# NL.net
KiCad netlist of a schematic drawn in Altium Designer
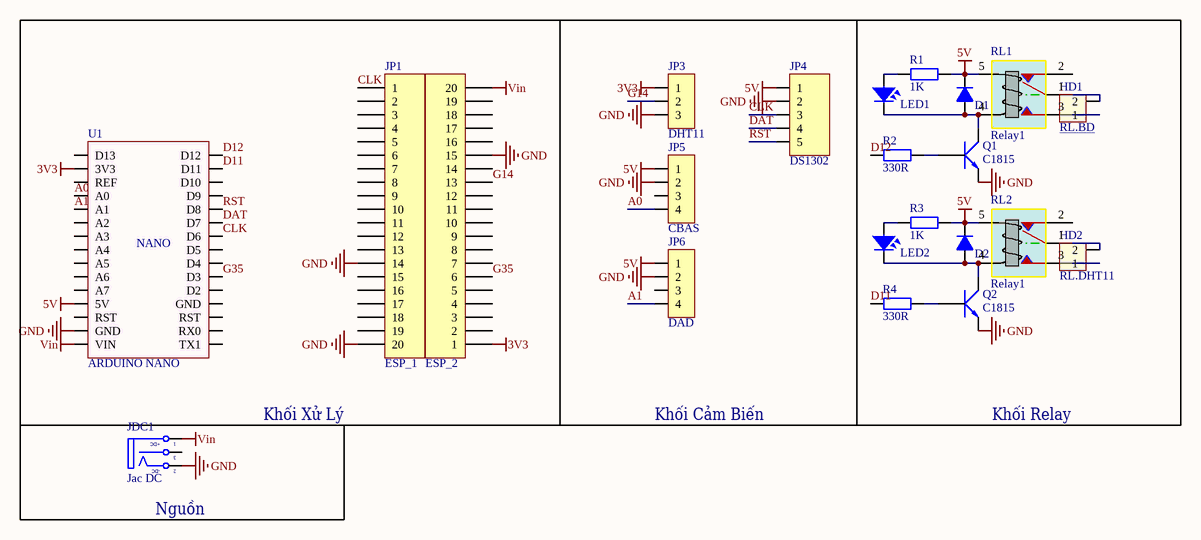
[diagram p0: NL.SchDoc]

(export (version "E")
  (design (tool "Eeschema 10.0.6"))
  (components
    (comp (ref "D1")
      (value "4007")
      (footprint "DIODE 1A")
      (description "Cắm")
      (libsource (lib "Altium_Lib_by_KhueNguyenCreator") (part "Diode 1N4007"))
    )
    (comp (ref "D2")
      (value "4007")
      (footprint "DIODE 1A")
      (description "Cắm")
      (libsource (lib "Altium_Lib_by_KhueNguyenCreator") (part "Diode 1N4007"))
    )
    (comp (ref "HD1")
      (value "RL.BD")
      (footprint "HED2")
      (description "Header 2 (Green)")
      (libsource (lib "syhaunguyen") (part "Hed2"))
    )
    (comp (ref "HD2")
      (value "RL.DHT11")
      (footprint "HED2")
      (description "Header 2 (Green)")
      (libsource (lib "syhaunguyen") (part "Hed2"))
    )
    (comp (ref "JDC1")
      (value "Jac DC")
      (footprint "DC-IN")
      (description "Jac DC input")
      (libsource (lib "syhaunguyen") (part "DCIN"))
    )
    (comp (ref "JP1")
      (value "ESP_1")
      (footprint "JP 1x20 CT")
      (description "Cắm")
      (libsource (lib "") (part "JP 1x20 2.54 Cai Thang_1"))
    )
    (comp (ref "JP2")
      (value "ESP_2")
      (footprint "JP 1x20 CT")
      (description "Cắm")
      (libsource (lib "Altium_Lib_by_KhueNguyenCreator") (part "JP 1x20 2.54 Cai Thang"))
    )
    (comp (ref "JP3")
      (value "DHT11")
      (footprint "JP 1x3 CT")
      (description "Cắm")
      (libsource (lib "Altium_Lib_by_KhueNguyenCreator") (part "JP 1x3 2.54 Cai Thang"))
    )
    (comp (ref "JP4")
      (value "DS1302")
      (footprint "JP 1x5 CT")
      (description "Cắm")
      (libsource (lib "Altium_Lib_by_KhueNguyenCreator") (part "JP 1x5 2.54 Cai Thang"))
    )
    (comp (ref "JP5")
      (value "CBAS")
      (footprint "JP 1x4 CT")
      (description "Cắm")
      (libsource (lib "Altium_Lib_by_KhueNguyenCreator") (part "JP 1x4 2.54 Cai Thang"))
    )
    (comp (ref "JP6")
      (value "DAD")
      (footprint "JP 1x4 CT")
      (description "Cắm")
      (libsource (lib "Altium_Lib_by_KhueNguyenCreator") (part "JP 1x4 2.54 Cai Thang"))
    )
    (comp (ref "LED1")
      (value "LED")
      (footprint "LED-3")
      (description "LED Single colour Green and Red")
      (libsource (lib "syhaunguyen") (part "LED"))
    )
    (comp (ref "LED2")
      (value "LED")
      (footprint "LED-3")
      (description "LED Single colour Green and Red")
      (libsource (lib "syhaunguyen") (part "LED"))
    )
    (comp (ref "Q1")
      (value "C1815")
      (footprint "TO92")
      (description "NPN transistor")
      (libsource (lib "Altium_Lib_by_KhueNguyenCreator") (part "C1815"))
    )
    (comp (ref "Q2")
      (value "C1815")
      (footprint "TO92")
      (description "NPN transistor")
      (libsource (lib "Altium_Lib_by_KhueNguyenCreator") (part "C1815"))
    )
    (comp (ref "R1")
      (value "1K")
      (footprint "R1/4W")
      (description "Resistor 1/4W")
      (libsource (lib "syhaunguyen") (part "R1/4W"))
    )
    (comp (ref "R2")
      (value "330R")
      (footprint "R1/4W")
      (description "Resistor 1/4W")
      (libsource (lib "syhaunguyen") (part "R1/4W"))
    )
    (comp (ref "R3")
      (value "1K")
      (footprint "R1/4W")
      (description "Resistor 1/4W")
      (libsource (lib "syhaunguyen") (part "R1/4W"))
    )
    (comp (ref "R4")
      (value "330R")
      (footprint "R1/4W")
      (description "Resistor 1/4W")
      (libsource (lib "syhaunguyen") (part "R1/4W"))
    )
    (comp (ref "RL1")
      (value "Relay1")
      (footprint "RELAY1")
      (description "Relay SPDT,10A - 12VDC 5 Pin")
      (libsource (lib "tham_khanh") (part "Relay1"))
    )
    (comp (ref "RL2")
      (value "Relay1")
      (footprint "RELAY1")
      (description "Relay SPDT,10A - 12VDC 5 Pin")
      (libsource (lib "tham_khanh") (part "Relay1"))
    )
    (comp (ref "U1")
      (value "ARDUINO NANO")
      (footprint "Arduino Nano")
      (description "ATMEGA328, ARDUINO NANO, EVAL BOARD")
      (libsource (lib "tham_khanh") (part "ARDUINO NANO"))
    )
  )
  (nets
    (net (code "1") (name "/A0") (class "Default")
      (node (ref "JP5") (pin "4") (pinfunction "4_4") (pintype "passive"))
      (node (ref "U1") (pin "A0") (pinfunction "A0_A0") (pintype "passive"))
    )
    (net (code "2") (name "/A1") (class "Default")
      (node (ref "JP6") (pin "4") (pinfunction "4_4") (pintype "passive"))
      (node (ref "U1") (pin "A1") (pinfunction "A1_A1") (pintype "passive"))
    )
    (net (code "3") (name "/CLK") (class "Default")
      (node (ref "JP1") (pin "1") (pinfunction "1_1") (pintype "passive"))
      (node (ref "JP4") (pin "3") (pinfunction "3_3") (pintype "passive"))
      (node (ref "U1") (pin "D6") (pinfunction "D6_D6") (pintype "passive"))
    )
    (net (code "4") (name "/D11") (class "Default")
      (node (ref "R4") (pin "1") (pinfunction "1_1") (pintype "passive"))
      (node (ref "U1") (pin "D11") (pinfunction "D11_D11") (pintype "passive"))
    )
    (net (code "5") (name "/D12") (class "Default")
      (node (ref "R2") (pin "1") (pinfunction "1_1") (pintype "passive"))
      (node (ref "U1") (pin "D12") (pinfunction "D12_D12") (pintype "passive"))
    )
    (net (code "6") (name "/DAT") (class "Default")
      (node (ref "JP4") (pin "4") (pinfunction "4_4") (pintype "passive"))
      (node (ref "U1") (pin "D7") (pinfunction "D7_D7") (pintype "passive"))
    )
    (net (code "7") (name "/G14") (class "Default")
      (node (ref "JP2") (pin "13") (pinfunction "13_13") (pintype "passive"))
      (node (ref "JP3") (pin "2") (pinfunction "2_2") (pintype "passive"))
    )
    (net (code "8") (name "/G35") (class "Default")
      (node (ref "JP2") (pin "6") (pinfunction "6_6") (pintype "passive"))
      (node (ref "U1") (pin "D3") (pinfunction "D3_D3") (pintype "passive"))
    )
    (net (code "9") (name "/RST") (class "Default")
      (node (ref "JP4") (pin "5") (pinfunction "5_5") (pintype "passive"))
      (node (ref "U1") (pin "D8") (pinfunction "D8_D8") (pintype "passive"))
    )
    (net (code "10") (name "3V3") (class "Default")
      (node (ref "JP2") (pin "1") (pinfunction "1_1") (pintype "passive"))
      (node (ref "JP3") (pin "1") (pinfunction "1_1") (pintype "passive"))
      (node (ref "U1") (pin "3V3") (pinfunction "3V3_3V3") (pintype "passive"))
    )
    (net (code "11") (name "5V") (class "Default")
      (node (ref "D1") (pin "2") (pinfunction "K_2") (pintype "passive"))
      (node (ref "D2") (pin "2") (pinfunction "K_2") (pintype "passive"))
      (node (ref "JP4") (pin "1") (pinfunction "1_1") (pintype "passive"))
      (node (ref "JP5") (pin "1") (pinfunction "1_1") (pintype "passive"))
      (node (ref "JP6") (pin "1") (pinfunction "1_1") (pintype "passive"))
      (node (ref "R1") (pin "2") (pinfunction "2_2") (pintype "passive"))
      (node (ref "R3") (pin "2") (pinfunction "2_2") (pintype "passive"))
      (node (ref "RL1") (pin "5") (pinfunction "5_5") (pintype "passive"))
      (node (ref "RL2") (pin "5") (pinfunction "5_5") (pintype "passive"))
      (node (ref "U1") (pin "5V") (pinfunction "5V_5V") (pintype "passive"))
    )
    (net (code "12") (name "GND") (class "Default")
      (node (ref "JDC1") (pin "2") (pinfunction "TN_2") (pintype "passive"))
      (node (ref "JP1") (pin "14") (pinfunction "14_14") (pintype "passive"))
      (node (ref "JP1") (pin "20") (pinfunction "20_20") (pintype "passive"))
      (node (ref "JP2") (pin "15") (pinfunction "15_15") (pintype "passive"))
      (node (ref "JP3") (pin "3") (pinfunction "3_3") (pintype "passive"))
      (node (ref "JP4") (pin "2") (pinfunction "2_2") (pintype "passive"))
      (node (ref "JP5") (pin "2") (pinfunction "2_2") (pintype "passive"))
      (node (ref "JP6") (pin "2") (pinfunction "2_2") (pintype "passive"))
      (node (ref "Q1") (pin "1") (pinfunction "E_1") (pintype "passive"))
      (node (ref "Q2") (pin "1") (pinfunction "E_1") (pintype "passive"))
      (node (ref "U1") (pin "GND") (pinfunction "GND_GND") (pintype "power_in"))
    )
    (net (code "13") (name "Net-(D1-A)") (class "Default")
      (node (ref "D1") (pin "1") (pinfunction "A_1") (pintype "passive"))
      (node (ref "LED1") (pin "2") (pinfunction "2_2") (pintype "passive"))
      (node (ref "Q1") (pin "2") (pinfunction "C_2") (pintype "passive"))
      (node (ref "RL1") (pin "4") (pinfunction "4_4") (pintype "passive"))
    )
    (net (code "14") (name "Net-(D2-A)") (class "Default")
      (node (ref "D2") (pin "1") (pinfunction "A_1") (pintype "passive"))
      (node (ref "LED2") (pin "2") (pinfunction "2_2") (pintype "passive"))
      (node (ref "Q2") (pin "2") (pinfunction "C_2") (pintype "passive"))
      (node (ref "RL2") (pin "4") (pinfunction "4_4") (pintype "passive"))
    )
    (net (code "15") (name "Net-(HD1-Pad1)") (class "Default")
      (node (ref "HD1") (pin "1") (pinfunction "1_1") (pintype "passive"))
      (node (ref "RL1") (pin "3") (pinfunction "3_3") (pintype "passive"))
    )
    (net (code "16") (name "Net-(HD1-Pad2)") (class "Default")
      (node (ref "HD1") (pin "2") (pinfunction "2_2") (pintype "passive"))
      (node (ref "RL1") (pin "1") (pinfunction "1_1") (pintype "passive"))
    )
    (net (code "17") (name "Net-(HD2-Pad1)") (class "Default")
      (node (ref "HD2") (pin "1") (pinfunction "1_1") (pintype "passive"))
      (node (ref "RL2") (pin "3") (pinfunction "3_3") (pintype "passive"))
    )
    (net (code "18") (name "Net-(HD2-Pad2)") (class "Default")
      (node (ref "HD2") (pin "2") (pinfunction "2_2") (pintype "passive"))
      (node (ref "RL2") (pin "1") (pinfunction "1_1") (pintype "passive"))
    )
    (net (code "19") (name "Net-(LED1-Pad1)") (class "Default")
      (node (ref "LED1") (pin "1") (pinfunction "1_1") (pintype "passive"))
      (node (ref "R1") (pin "1") (pinfunction "1_1") (pintype "passive"))
    )
    (net (code "20") (name "Net-(LED2-Pad1)") (class "Default")
      (node (ref "LED2") (pin "1") (pinfunction "1_1") (pintype "passive"))
      (node (ref "R3") (pin "1") (pinfunction "1_1") (pintype "passive"))
    )
    (net (code "21") (name "Net-(Q1-B)") (class "Default")
      (node (ref "Q1") (pin "3") (pinfunction "B_3") (pintype "passive"))
      (node (ref "R2") (pin "2") (pinfunction "2_2") (pintype "passive"))
    )
    (net (code "22") (name "Net-(Q2-B)") (class "Default")
      (node (ref "Q2") (pin "3") (pinfunction "B_3") (pintype "passive"))
      (node (ref "R4") (pin "2") (pinfunction "2_2") (pintype "passive"))
    )
    (net (code "23") (name "Vin") (class "Default")
      (node (ref "JDC1") (pin "1") (pinfunction "T_1") (pintype "passive"))
      (node (ref "JP2") (pin "20") (pinfunction "20_20") (pintype "passive"))
      (node (ref "U1") (pin "VIN") (pinfunction "VIN_VIN") (pintype "passive"))
    )
    (net (code "24") (name "unconnected-(JDC1-S-Pad3)") (class "Default")
      (node (ref "JDC1") (pin "3") (pinfunction "S_3") (pintype "power_in"))
    )
    (net (code "25") (name "unconnected-(JP1-Pad2)") (class "Default")
      (node (ref "JP1") (pin "2") (pinfunction "2_2") (pintype "passive"))
    )
    (net (code "26") (name "unconnected-(JP1-Pad3)") (class "Default")
      (node (ref "JP1") (pin "3") (pinfunction "3_3") (pintype "passive"))
    )
    (net (code "27") (name "unconnected-(JP1-Pad4)") (class "Default")
      (node (ref "JP1") (pin "4") (pinfunction "4_4") (pintype "passive"))
    )
    (net (code "28") (name "unconnected-(JP1-Pad5)") (class "Default")
      (node (ref "JP1") (pin "5") (pinfunction "5_5") (pintype "passive"))
    )
    (net (code "29") (name "unconnected-(JP1-Pad6)") (class "Default")
      (node (ref "JP1") (pin "6") (pinfunction "6_6") (pintype "passive"))
    )
    (net (code "30") (name "unconnected-(JP1-Pad7)") (class "Default")
      (node (ref "JP1") (pin "7") (pinfunction "7_7") (pintype "passive"))
    )
    (net (code "31") (name "unconnected-(JP1-Pad8)") (class "Default")
      (node (ref "JP1") (pin "8") (pinfunction "8_8") (pintype "passive"))
    )
    (net (code "32") (name "unconnected-(JP1-Pad9)") (class "Default")
      (node (ref "JP1") (pin "9") (pinfunction "9_9") (pintype "passive"))
    )
    (net (code "33") (name "unconnected-(JP1-Pad10)") (class "Default")
      (node (ref "JP1") (pin "10") (pinfunction "10_10") (pintype "passive"))
    )
    (net (code "34") (name "unconnected-(JP1-Pad11)") (class "Default")
      (node (ref "JP1") (pin "11") (pinfunction "11_11") (pintype "passive"))
    )
    (net (code "35") (name "unconnected-(JP1-Pad12)") (class "Default")
      (node (ref "JP1") (pin "12") (pinfunction "12_12") (pintype "passive"))
    )
    (net (code "36") (name "unconnected-(JP1-Pad13)") (class "Default")
      (node (ref "JP1") (pin "13") (pinfunction "13_13") (pintype "passive"))
    )
    (net (code "37") (name "unconnected-(JP1-Pad15)") (class "Default")
      (node (ref "JP1") (pin "15") (pinfunction "15_15") (pintype "passive"))
    )
    (net (code "38") (name "unconnected-(JP1-Pad16)") (class "Default")
      (node (ref "JP1") (pin "16") (pinfunction "16_16") (pintype "passive"))
    )
    (net (code "39") (name "unconnected-(JP1-Pad17)") (class "Default")
      (node (ref "JP1") (pin "17") (pinfunction "17_17") (pintype "passive"))
    )
    (net (code "40") (name "unconnected-(JP1-Pad18)") (class "Default")
      (node (ref "JP1") (pin "18") (pinfunction "18_18") (pintype "passive"))
    )
    (net (code "41") (name "unconnected-(JP1-Pad19)") (class "Default")
      (node (ref "JP1") (pin "19") (pinfunction "19_19") (pintype "passive"))
    )
    (net (code "42") (name "unconnected-(JP2-Pad2)") (class "Default")
      (node (ref "JP2") (pin "2") (pinfunction "2_2") (pintype "passive"))
    )
    (net (code "43") (name "unconnected-(JP2-Pad3)") (class "Default")
      (node (ref "JP2") (pin "3") (pinfunction "3_3") (pintype "passive"))
    )
    (net (code "44") (name "unconnected-(JP2-Pad4)") (class "Default")
      (node (ref "JP2") (pin "4") (pinfunction "4_4") (pintype "passive"))
    )
    (net (code "45") (name "unconnected-(JP2-Pad5)") (class "Default")
      (node (ref "JP2") (pin "5") (pinfunction "5_5") (pintype "passive"))
    )
    (net (code "46") (name "unconnected-(JP2-Pad7)") (class "Default")
      (node (ref "JP2") (pin "7") (pinfunction "7_7") (pintype "passive"))
    )
    (net (code "47") (name "unconnected-(JP2-Pad8)") (class "Default")
      (node (ref "JP2") (pin "8") (pinfunction "8_8") (pintype "passive"))
    )
    (net (code "48") (name "unconnected-(JP2-Pad9)") (class "Default")
      (node (ref "JP2") (pin "9") (pinfunction "9_9") (pintype "passive"))
    )
    (net (code "49") (name "unconnected-(JP2-Pad10)") (class "Default")
      (node (ref "JP2") (pin "10") (pinfunction "10_10") (pintype "passive"))
    )
    (net (code "50") (name "unconnected-(JP2-Pad11)") (class "Default")
      (node (ref "JP2") (pin "11") (pinfunction "11_11") (pintype "passive"))
    )
    (net (code "51") (name "unconnected-(JP2-Pad12)") (class "Default")
      (node (ref "JP2") (pin "12") (pinfunction "12_12") (pintype "passive"))
    )
    (net (code "52") (name "unconnected-(JP2-Pad14)") (class "Default")
      (node (ref "JP2") (pin "14") (pinfunction "14_14") (pintype "passive"))
    )
    (net (code "53") (name "unconnected-(JP2-Pad16)") (class "Default")
      (node (ref "JP2") (pin "16") (pinfunction "16_16") (pintype "passive"))
    )
    (net (code "54") (name "unconnected-(JP2-Pad17)") (class "Default")
      (node (ref "JP2") (pin "17") (pinfunction "17_17") (pintype "passive"))
    )
    (net (code "55") (name "unconnected-(JP2-Pad18)") (class "Default")
      (node (ref "JP2") (pin "18") (pinfunction "18_18") (pintype "passive"))
    )
    (net (code "56") (name "unconnected-(JP2-Pad19)") (class "Default")
      (node (ref "JP2") (pin "19") (pinfunction "19_19") (pintype "passive"))
    )
    (net (code "57") (name "unconnected-(JP5-Pad3)") (class "Default")
      (node (ref "JP5") (pin "3") (pinfunction "3_3") (pintype "passive"))
    )
    (net (code "58") (name "unconnected-(JP6-Pad3)") (class "Default")
      (node (ref "JP6") (pin "3") (pinfunction "3_3") (pintype "passive"))
    )
    (net (code "59") (name "unconnected-(RL1-Pad2)") (class "Default")
      (node (ref "RL1") (pin "2") (pinfunction "2_2") (pintype "passive"))
    )
    (net (code "60") (name "unconnected-(RL2-Pad2)") (class "Default")
      (node (ref "RL2") (pin "2") (pinfunction "2_2") (pintype "passive"))
    )
    (net (code "61") (name "unconnected-(U1-GND-PadAGND)") (class "Default")
      (node (ref "U1") (pin "AGND") (pinfunction "GND_AGND") (pintype "power_in"))
    )
    (net (code "62") (name "unconnected-(U1-PadA2)") (class "Default")
      (node (ref "U1") (pin "A2") (pinfunction "A2_A2") (pintype "passive"))
    )
    (net (code "63") (name "unconnected-(U1-PadA3)") (class "Default")
      (node (ref "U1") (pin "A3") (pinfunction "A3_A3") (pintype "passive"))
    )
    (net (code "64") (name "unconnected-(U1-PadA4)") (class "Default")
      (node (ref "U1") (pin "A4") (pinfunction "A4_A4") (pintype "passive"))
    )
    (net (code "65") (name "unconnected-(U1-PadA5)") (class "Default")
      (node (ref "U1") (pin "A5") (pinfunction "A5_A5") (pintype "passive"))
    )
    (net (code "66") (name "unconnected-(U1-PadA6)") (class "Default")
      (node (ref "U1") (pin "A6") (pinfunction "A6_A6") (pintype "passive"))
    )
    (net (code "67") (name "unconnected-(U1-PadA7)") (class "Default")
      (node (ref "U1") (pin "A7") (pinfunction "A7_A7") (pintype "passive"))
    )
    (net (code "68") (name "unconnected-(U1-PadD2)") (class "Default")
      (node (ref "U1") (pin "D2") (pinfunction "D2_D2") (pintype "passive"))
    )
    (net (code "69") (name "unconnected-(U1-PadD4)") (class "Default")
      (node (ref "U1") (pin "D4") (pinfunction "D4_D4") (pintype "passive"))
    )
    (net (code "70") (name "unconnected-(U1-PadD5)") (class "Default")
      (node (ref "U1") (pin "D5") (pinfunction "D5_D5") (pintype "passive"))
    )
    (net (code "71") (name "unconnected-(U1-PadD9)") (class "Default")
      (node (ref "U1") (pin "D9") (pinfunction "D9_D9") (pintype "passive"))
    )
    (net (code "72") (name "unconnected-(U1-PadD10)") (class "Default")
      (node (ref "U1") (pin "D10") (pinfunction "D10_D10") (pintype "passive"))
    )
    (net (code "73") (name "unconnected-(U1-PadD13)") (class "Default")
      (node (ref "U1") (pin "D13") (pinfunction "D13_D13") (pintype "passive"))
    )
    (net (code "74") (name "unconnected-(U1-PadREF)") (class "Default")
      (node (ref "U1") (pin "REF") (pinfunction "REF_REF") (pintype "passive"))
    )
    (net (code "75") (name "unconnected-(U1-PadRST)") (class "Default")
      (node (ref "U1") (pin "RST") (pinfunction "RST_RST") (pintype "passive"))
    )
    (net (code "76") (name "unconnected-(U1-PadRX0)") (class "Default")
      (node (ref "U1") (pin "RX0") (pinfunction "RX0_RX0") (pintype "passive"))
    )
    (net (code "77") (name "unconnected-(U1-PadTX1)") (class "Default")
      (node (ref "U1") (pin "TX1") (pinfunction "TX1_TX1") (pintype "passive"))
    )
    (net (code "78") (name "unconnected-(U1-RST-PadARST)") (class "Default")
      (node (ref "U1") (pin "ARST") (pinfunction "RST_ARST") (pintype "passive"))
    )
  )
)
